# 3V3_buck.net
KiCad netlist of a schematic drawn in Altium Designer
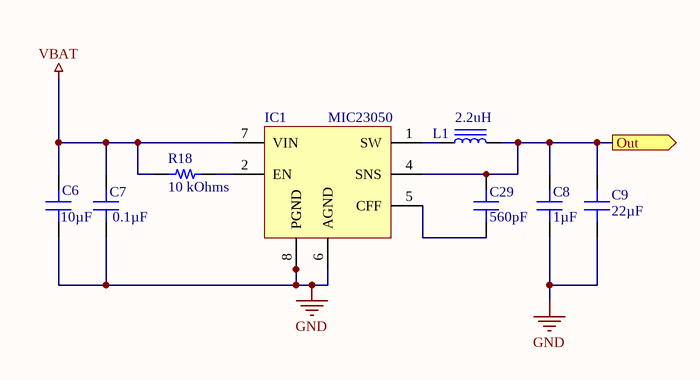
[diagram p0: 3V3_buck.SchDoc]

(export (version "E")
  (design (tool "Eeschema 10.0.6"))
  (components
    (comp (ref "C6")
      (value "10µF")
      (footprint "CAP 0805_2012")
      (description "CAP CER 10UF 25V X7S 0805")
      (fields
        (field (name "PART NUMBER") "C2012X7S1E106K125AC")
        (field (name "MANUFACTURER") "TDK Corporation")
      )
      (libsource (lib "Celestial Altium Library - altium_library") (part "Capacitor"))
    )
    (comp (ref "C7")
      (value "0.1µF")
      (footprint "CAP 0603_1608")
      (description "CAP CER 0.1UF 100V 0603 EPOXY")
      (fields
        (field (name "PART NUMBER") "GCG188R92A104KA03D")
        (field (name "MANUFACTURER") "Murata Electronics")
      )
      (libsource (lib "Celestial Altium Library - altium_library") (part "Capacitor"))
    )
    (comp (ref "C8")
      (value "1µF")
      (footprint "CAP 0603_1608")
      (description "CAP CER 1UF 25V X7R 0603")
      (fields
        (field (name "PART NUMBER") "GCJ188R71E105KA01D")
        (field (name "MANUFACTURER") "Murata Electronics")
      )
      (libsource (lib "Celestial Altium Library - altium_library") (part "Capacitor"))
    )
    (comp (ref "C9")
      (value "22µF")
      (footprint "CAP 0805_2012")
      (description "CAP CER 22UF 16V X5R 0805")
      (fields
        (field (name "PART NUMBER") "CL21A226MOQNNNE")
        (field (name "MANUFACTURER") "Samsung Electro-Mechanics")
      )
      (libsource (lib "Celestial Altium Library - altium_library") (part "Capacitor"))
    )
    (comp (ref "C29")
      (value "560pF")
      (footprint "CAP 0603_1608")
      (description "CAP CER 1UF 25V X7R 0603")
      (fields
        (field (name "PART NUMBER") "GCJ188R71E105KA01D")
        (field (name "MANUFACTURER") "Murata Electronics")
      )
      (libsource (lib "Celestial Altium Library - altium_library") (part "Capacitor"))
    )
    (comp (ref "IC1") (value "MIC23050") (footprint "MLF-8 2x2mm") (libsource (lib "IC") (part "MIC23050")))
    (comp (ref "L1")
      (value "2.2uH")
      (footprint "IND 0806_2016")
      (description "FIXED IND 6.8UH 530MA 864 MOHM")
      (fields
        (field (name "PART NUMBER") "LQH2MPN6R8MGRL")
        (field (name "MANUFACTURER") "Murata Electronics")
      )
      (libsource (lib "Celestial Altium Library - altium_library") (part "Inductor"))
    )
    (comp (ref "R18")
      (value "10 kOhms")
      (footprint "RES 0603_1608")
      (description "RES 10K OHM 0.1% 1/16W 0603")
      (fields
        (field (name "PART NUMBER") "RNCS0603BKE10K0")
        (field (name "MANUFACTURER") "Stackpole Electronics Inc")
      )
      (libsource (lib "Celestial Altium Library - altium_library") (part "Resistor"))
    )
  )
  (nets
    (net (code "1") (name "/Out") (class "Default")
      (node (ref "C29") (pin "2") (pinfunction "2_2") (pintype "passive"))
      (node (ref "C8") (pin "2") (pinfunction "2_2") (pintype "passive"))
      (node (ref "C9") (pin "2") (pinfunction "2_2") (pintype "passive"))
      (node (ref "IC1") (pin "4") (pinfunction "SNS_4") (pintype "passive"))
      (node (ref "L1") (pin "2") (pinfunction "2_2") (pintype "passive"))
    )
    (net (code "2") (name "GND") (class "Default")
      (node (ref "C6") (pin "1") (pinfunction "1_1") (pintype "passive"))
      (node (ref "C7") (pin "2") (pinfunction "2_2") (pintype "passive"))
      (node (ref "C8") (pin "1") (pinfunction "1_1") (pintype "passive"))
      (node (ref "C9") (pin "1") (pinfunction "1_1") (pintype "passive"))
      (node (ref "IC1") (pin "6") (pinfunction "AGND_6") (pintype "passive"))
      (node (ref "IC1") (pin "8") (pinfunction "PGND_8") (pintype "passive"))
      (node (ref "IC1") (pin "9") (pinfunction "PGND_9") (pintype "passive"))
    )
    (net (code "3") (name "Net-(IC1-CFF)") (class "Default")
      (node (ref "C29") (pin "1") (pinfunction "1_1") (pintype "passive"))
      (node (ref "IC1") (pin "5") (pinfunction "CFF_5") (pintype "passive"))
    )
    (net (code "4") (name "Net-(IC1-EN)") (class "Default")
      (node (ref "IC1") (pin "2") (pinfunction "EN_2") (pintype "passive"))
      (node (ref "R18") (pin "1") (pinfunction "1_1") (pintype "passive"))
    )
    (net (code "5") (name "Net-(IC1-SW)") (class "Default")
      (node (ref "IC1") (pin "1") (pinfunction "SW_1") (pintype "passive"))
      (node (ref "L1") (pin "1") (pinfunction "1_1") (pintype "passive"))
    )
    (net (code "6") (name "VBAT") (class "Default")
      (node (ref "C6") (pin "2") (pinfunction "2_2") (pintype "passive"))
      (node (ref "C7") (pin "1") (pinfunction "1_1") (pintype "passive"))
      (node (ref "IC1") (pin "7") (pinfunction "VIN_7") (pintype "passive"))
      (node (ref "R18") (pin "2") (pinfunction "2_2") (pintype "passive"))
    )
  )
)
